# PWR.net
KiCad netlist of a schematic drawn in Altium Designer
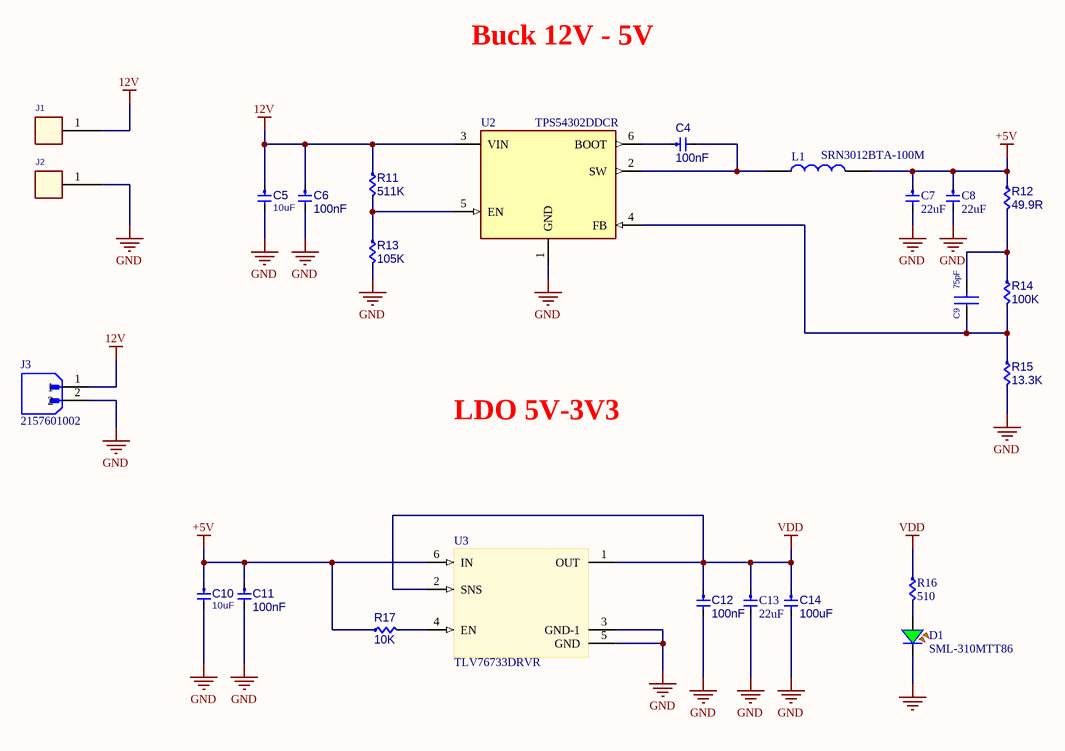
[diagram p0: PWR.SchDoc]

(export (version "E")
  (design (tool "Eeschema 10.0.6"))
  (components
    (comp (ref "C4")
      (value "CC0402KRX5R9BB104")
      (footprint "CAP0402")
      (description "CAP CER 0.1UF 50V X5R 0402")
      (fields
        (field (name "MANUFACTURER") "Yageo")
        (field (name "TOLERANCE") "10%")
        (field (name "CAPACITANCE") "100nF")
      )
      (libsource (lib "rtr") (part "CMP-00265-1"))
    )
    (comp (ref "C5")
      (value "GRM188R6YA106MA73D")
      (footprint "CAP0603")
      (description "CAP CER 10UF 35V X5R 0603")
      (fields
        (field (name "TOLERANCE") "20%")
        (field (name "VOLTAGE") "35V")
        (field (name "CAPACITANCE") "10uF")
      )
      (libsource (lib "rtr") (part "CMP-01031-1"))
    )
    (comp (ref "C6")
      (value "CC0402KRX5R9BB104")
      (footprint "CAP0402")
      (description "CAP CER 0.1UF 50V X5R 0402")
      (fields
        (field (name "MANUFACTURER") "Yageo")
        (field (name "TOLERANCE") "10%")
        (field (name "CAPACITANCE") "100nF")
      )
      (libsource (lib "rtr") (part "CMP-00265-1"))
    )
    (comp (ref "C7")
      (value "GRM158R61A226ME15D")
      (footprint "CAP0402")
      (description "CAP CER 22UF 10V X5R 0402")
      (fields
        (field (name "VOLTAGE") "10V")
        (field (name "TOLERANCE") "10%")
        (field (name "CAPACITANCE") "22uF")
      )
      (libsource (lib "CH961_CARRIER") (part "CMP-00520-1"))
    )
    (comp (ref "C8")
      (value "GRM158R61A226ME15D")
      (footprint "CAP0402")
      (description "CAP CER 22UF 10V X5R 0402")
      (fields
        (field (name "VOLTAGE") "10V")
        (field (name "TOLERANCE") "10%")
        (field (name "CAPACITANCE") "22uF")
      )
      (libsource (lib "CH961_CARRIER") (part "CMP-00520-1"))
    )
    (comp (ref "C9")
      (value "75pF")
      (footprint "CAP0402")
      (description "CAP CER 75PF 25V C0G/NP0 0402")
      (fields (field (name "MANUFACTURER") "YAGEO") (field (name "TOLERANCE") "5%"))
      (libsource (lib "motor MB1419") (part "CAP_Dup1_16"))
    )
    (comp (ref "C10")
      (value "GRM188R6YA106MA73D")
      (footprint "CAP0603")
      (description "CAP CER 10UF 35V X5R 0603")
      (fields
        (field (name "TOLERANCE") "20%")
        (field (name "VOLTAGE") "35V")
        (field (name "CAPACITANCE") "10uF")
      )
      (libsource (lib "rtr") (part "CMP-01031-1"))
    )
    (comp (ref "C11")
      (value "CC0402KRX5R9BB104")
      (footprint "CAP0402")
      (description "CAP CER 0.1UF 50V X5R 0402")
      (fields
        (field (name "MANUFACTURER") "Yageo")
        (field (name "TOLERANCE") "10%")
        (field (name "CAPACITANCE") "100nF")
      )
      (libsource (lib "rtr") (part "CMP-00265-1"))
    )
    (comp (ref "C12")
      (value "CC0402KRX5R9BB104")
      (footprint "CAP0402")
      (description "CAP CER 0.1UF 50V X5R 0402")
      (fields
        (field (name "MANUFACTURER") "Yageo")
        (field (name "TOLERANCE") "10%")
        (field (name "CAPACITANCE") "100nF")
      )
      (libsource (lib "rtr") (part "CMP-00265-1"))
    )
    (comp (ref "C13")
      (value "GRM158R61A226ME15D")
      (footprint "CAP0402")
      (description "CAP CER 22UF 10V X5R 0402")
      (fields
        (field (name "VOLTAGE") "10V")
        (field (name "TOLERANCE") "10%")
        (field (name "CAPACITANCE") "22uF")
      )
      (libsource (lib "CH961_CARRIER") (part "CMP-00520-1"))
    )
    (comp (ref "C14")
      (value "CL21A107MQYNNWE")
      (footprint "CAP0805")
      (description "CAP CER 100UF 6.3V X5R 0805")
      (fields (field (name "CAPACITANCE") "100uF") (field (name "TOLERANCE") "20%"))
      (libsource (lib "rtr") (part "CMP-00446-1"))
    )
    (comp (ref "D1")
      (value "SML-310MTT86")
      (footprint "LED0603 RED")
      (description "LED GREEN CLEAR 0603 SMD")
      (libsource (lib "HeraJetson_Modified") (part "CMP-01130-2"))
    )
    (comp (ref "J1")
      (value "CON1")
      (footprint "ESC PAD 3X4")
      (description "SOLDER PADS")
      (libsource (lib "motor MB1419") (part "CON1"))
    )
    (comp (ref "J2")
      (value "CON1")
      (footprint "ESC PAD 3X4")
      (description "SOLDER PADS")
      (libsource (lib "motor MB1419") (part "CON1"))
    )
    (comp (ref "J3")
      (value "2157601002")
      (footprint "MOLEX_2157601002")
      (fields (field (name "MF") "{'manufacturer': u'Molex'}"))
      (libsource (lib "2157601002") (part "2157601002"))
    )
    (comp (ref "L1")
      (value "SRN3012BTA-100M")
      (footprint "SRN3012BTA-100M")
      (description "10uH")
      (libsource (lib "SRN3012BTA-330M") (part "SRN3012BTA-330M"))
    )
    (comp (ref "R11")
      (value "511K")
      (footprint "RES0402")
      (description "RES SMD 511K OHM 1% 1/16W 0402")
      (fields (field (name "MANUFACTURER") "Yageo") (field (name "TOLERANCE") "1%"))
      (libsource (lib "rtr") (part "CMP-00299-1_1"))
    )
    (comp (ref "R12")
      (value "49.9R")
      (footprint "RES0402")
      (description "RES SMD 49.9R OHM 1% 1/16W 0402")
      (fields (field (name "MANUFACTURER") "Yageo") (field (name "TOLERANCE") "1%"))
      (libsource (lib "rtr") (part "CMP-00299-1_1"))
    )
    (comp (ref "R13")
      (value "105K")
      (footprint "RES0402")
      (description "RES SMD 105K OHM 1% 1/16W 0402")
      (fields (field (name "MANUFACTURER") "Yageo") (field (name "TOLERANCE") "1%"))
      (libsource (lib "rtr") (part "CMP-00299-1_1"))
    )
    (comp (ref "R14")
      (value "100K")
      (footprint "RES0402")
      (description "RES SMD 100K OHM 1% 1/16W 0402")
      (fields (field (name "MANUFACTURER") "Yageo") (field (name "TOLERANCE") "1%"))
      (libsource (lib "rtr") (part "CMP-00299-1_1"))
    )
    (comp (ref "R15")
      (value "13.3K")
      (footprint "RES0402")
      (description "RES SMD 100K OHM 1% 1/16W 0402")
      (fields (field (name "MANUFACTURER") "Yageo") (field (name "TOLERANCE") "1%"))
      (libsource (lib "rtr") (part "CMP-00299-1_1"))
    )
    (comp (ref "R16")
      (value "RT0402FRE07510RL")
      (footprint "RES0402")
      (description "RES SMD 510 OHM 1% 1/16W 0402")
      (fields
        (field (name "MANUFACTURER") "Yageo")
        (field (name "TOLERANCE") "1%")
        (field (name "RESISTANCE") "510")
      )
      (libsource (lib "CH961_CARRIER") (part "RC0402FR-0722KL"))
    )
    (comp (ref "R17")
      (value "10K")
      (footprint "RES0402")
      (description "RES SMD 100K OHM 1% 1/16W 0402")
      (fields (field (name "MANUFACTURER") "Yageo") (field (name "TOLERANCE") "1%"))
      (libsource (lib "rtr") (part "CMP-00299-1_1"))
    )
    (comp (ref "U2")
      (value "TPS54302DDCR")
      (footprint "TPS563200DDCR")
      (description "4.5-V to 28-V Input, 3-A Output, EMI Friendly Synchronous Step-Down Converter")
      (fields (field (name "MF") "Texas Instruments"))
      (libsource (lib "TPS54302DDCR") (part "TPS54302DDCR"))
    )
    (comp (ref "U3")
      (value "TLV76733DRVR")
      (footprint "TLV76733DRVR")
      (description "Adjustable- and fixed-output, 1-A, 16-V, positive-voltage low-dropout (LDO) linear regulator")
      (fields (field (name "MF") "Texas Instruments"))
      (libsource (lib "TLV76733DRVR") (part "TLV76733DRVR"))
    )
  )
  (nets
    (net (code "1") (name "+5V") (class "Default")
      (node (ref "C10") (pin "1") (pinfunction "1_1") (pintype "passive"))
      (node (ref "C11") (pin "1") (pinfunction "1_1") (pintype "passive"))
      (node (ref "C7") (pin "1") (pinfunction "1_1") (pintype "passive"))
      (node (ref "C8") (pin "1") (pinfunction "1_1") (pintype "passive"))
      (node (ref "L1") (pin "2") (pinfunction "2_2") (pintype "passive"))
      (node (ref "R12") (pin "1") (pinfunction "1_1") (pintype "passive"))
      (node (ref "R17") (pin "1") (pinfunction "1_1") (pintype "passive"))
      (node (ref "U3") (pin "6") (pinfunction "IN_6") (pintype "input"))
    )
    (net (code "2") (name "12V") (class "Default")
      (node (ref "C5") (pin "1") (pinfunction "1_1") (pintype "passive"))
      (node (ref "C6") (pin "1") (pinfunction "1_1") (pintype "passive"))
      (node (ref "J1") (pin "1") (pinfunction "1_1") (pintype "passive"))
      (node (ref "J3") (pin "1") (pinfunction "1_1") (pintype "passive"))
      (node (ref "R11") (pin "1") (pinfunction "1_1") (pintype "passive"))
      (node (ref "U2") (pin "3") (pinfunction "VIN_3") (pintype "power_in"))
    )
    (net (code "3") (name "GND") (class "Default")
      (node (ref "C10") (pin "2") (pinfunction "2_2") (pintype "passive"))
      (node (ref "C11") (pin "2") (pinfunction "2_2") (pintype "passive"))
      (node (ref "C12") (pin "2") (pinfunction "2_2") (pintype "passive"))
      (node (ref "C13") (pin "2") (pinfunction "2_2") (pintype "passive"))
      (node (ref "C14") (pin "2") (pinfunction "2_2") (pintype "passive"))
      (node (ref "C5") (pin "2") (pinfunction "2_2") (pintype "passive"))
      (node (ref "C6") (pin "2") (pinfunction "2_2") (pintype "passive"))
      (node (ref "C7") (pin "2") (pinfunction "2_2") (pintype "passive"))
      (node (ref "C8") (pin "2") (pinfunction "2_2") (pintype "passive"))
      (node (ref "D1") (pin "1") (pinfunction "1_1") (pintype "passive"))
      (node (ref "J2") (pin "1") (pinfunction "1_1") (pintype "passive"))
      (node (ref "J3") (pin "2") (pinfunction "2_2") (pintype "passive"))
      (node (ref "R13") (pin "2") (pinfunction "2_2") (pintype "passive"))
      (node (ref "R15") (pin "2") (pinfunction "2_2") (pintype "passive"))
      (node (ref "U2") (pin "1") (pinfunction "GND_1") (pintype "power_in"))
      (node (ref "U3") (pin "3") (pinfunction "GND-1_3") (pintype "power_in"))
      (node (ref "U3") (pin "5") (pinfunction "GND_5") (pintype "power_in"))
    )
    (net (code "4") (name "Net-(C9-Pad2)") (class "Default")
      (node (ref "C9") (pin "2") (pinfunction "2_2") (pintype "passive"))
      (node (ref "R12") (pin "2") (pinfunction "2_2") (pintype "passive"))
      (node (ref "R14") (pin "1") (pinfunction "1_1") (pintype "passive"))
    )
    (net (code "5") (name "Net-(D1-Pad2)") (class "Default")
      (node (ref "D1") (pin "2") (pinfunction "2_2") (pintype "passive"))
      (node (ref "R16") (pin "2") (pinfunction "2_2") (pintype "passive"))
    )
    (net (code "6") (name "Net-(U2-BOOT)") (class "Default")
      (node (ref "C4") (pin "1") (pinfunction "1_1") (pintype "passive"))
      (node (ref "U2") (pin "6") (pinfunction "BOOT_6") (pintype "output"))
    )
    (net (code "7") (name "Net-(U2-EN)") (class "Default")
      (node (ref "R11") (pin "2") (pinfunction "2_2") (pintype "passive"))
      (node (ref "R13") (pin "1") (pinfunction "1_1") (pintype "passive"))
      (node (ref "U2") (pin "5") (pinfunction "EN_5") (pintype "input"))
    )
    (net (code "8") (name "Net-(U2-FB)") (class "Default")
      (node (ref "C9") (pin "1") (pinfunction "1_1") (pintype "passive"))
      (node (ref "R14") (pin "2") (pinfunction "2_2") (pintype "passive"))
      (node (ref "R15") (pin "1") (pinfunction "1_1") (pintype "passive"))
      (node (ref "U2") (pin "4") (pinfunction "FB_4") (pintype "input"))
    )
    (net (code "9") (name "Net-(U2-SW)") (class "Default")
      (node (ref "C4") (pin "2") (pinfunction "2_2") (pintype "passive"))
      (node (ref "L1") (pin "1") (pinfunction "1_1") (pintype "passive"))
      (node (ref "U2") (pin "2") (pinfunction "SW_2") (pintype "output"))
    )
    (net (code "10") (name "Net-(U3-EN)") (class "Default")
      (node (ref "R17") (pin "2") (pinfunction "2_2") (pintype "passive"))
      (node (ref "U3") (pin "4") (pinfunction "EN_4") (pintype "input"))
    )
    (net (code "11") (name "VDD") (class "Default")
      (node (ref "C12") (pin "1") (pinfunction "1_1") (pintype "passive"))
      (node (ref "C13") (pin "1") (pinfunction "1_1") (pintype "passive"))
      (node (ref "C14") (pin "1") (pinfunction "1_1") (pintype "passive"))
      (node (ref "R16") (pin "1") (pinfunction "1_1") (pintype "passive"))
      (node (ref "U3") (pin "1") (pinfunction "OUT_1") (pintype "power_in"))
      (node (ref "U3") (pin "2") (pinfunction "SNS_2") (pintype "input"))
    )
  )
)
